# Motor_Driver.net
KiCad netlist of a schematic drawn in EAGLE
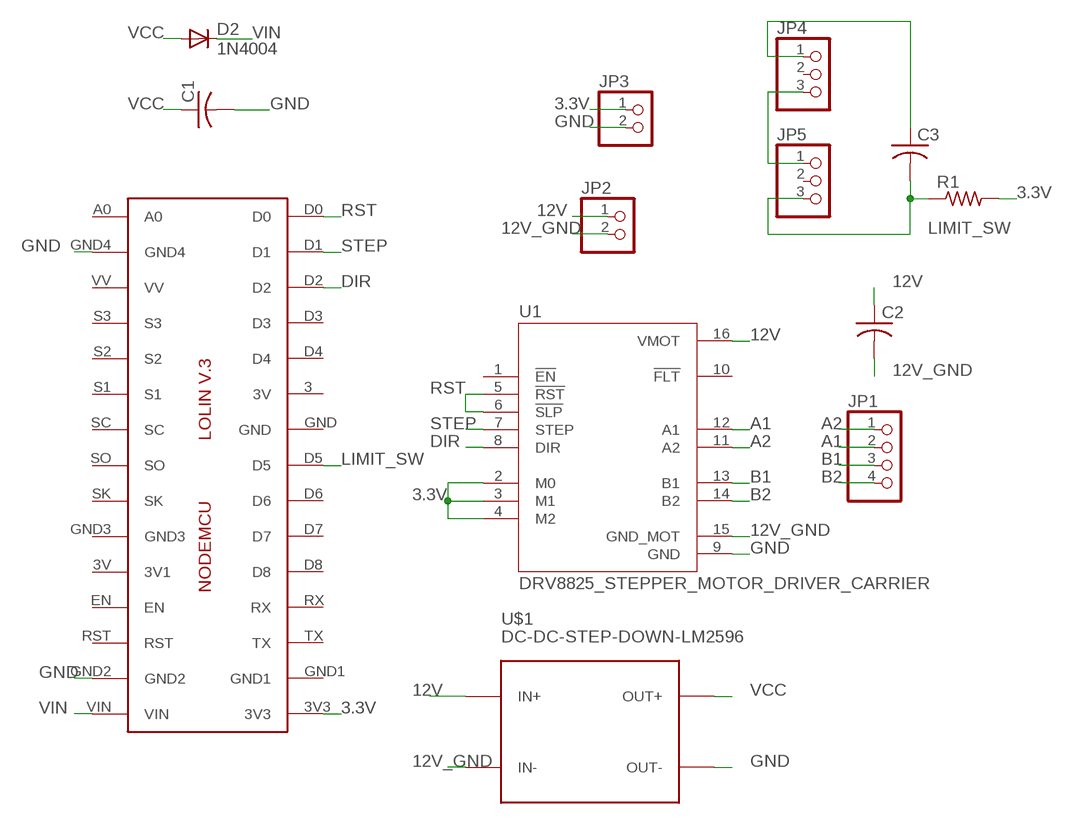
[diagram p0: schematic, sheet 1]

(export (version "E")
  (design (tool "Eeschema 10.0.6"))
  (components
    (comp (ref "C1")
      (value "C-US025-040X050")
      (footprint "eagle-import:C025-040X050")
      (libsource (lib "eagle-import") (part "C-US025-040X050"))
    )
    (comp (ref "C2")
      (value "C-US050-035X075")
      (footprint "eagle-import:C050-035X075")
      (libsource (lib "eagle-import") (part "C-US050-035X075"))
    )
    (comp (ref "C3")
      (value "C-US050-035X075")
      (footprint "eagle-import:C050-035X075")
      (libsource (lib "eagle-import") (part "C-US050-035X075"))
    )
    (comp (ref "D2")
      (value "1N4004")
      (footprint "eagle-import:DO41-10")
      (libsource (lib "eagle-import") (part "1N4004"))
    )
    (comp (ref "IC1")
      (value "LOLINV3")
      (footprint "eagle-import:LOLINV3")
      (libsource (lib "eagle-import") (part "LOLINV3"))
    )
    (comp (ref "JP1")
      (value "PINHD-1X4")
      (footprint "eagle-import:1X04")
      (libsource (lib "eagle-import") (part "PINHD-1X4"))
    )
    (comp (ref "JP2")
      (value "PINHD-1X2")
      (footprint "eagle-import:1X02")
      (libsource (lib "eagle-import") (part "PINHD-1X2"))
    )
    (comp (ref "JP3")
      (value "PINHD-1X2")
      (footprint "eagle-import:1X02")
      (libsource (lib "eagle-import") (part "PINHD-1X2"))
    )
    (comp (ref "JP4")
      (value "PINHD-1X3CB")
      (footprint "eagle-import:1X03-CLEANBIG")
      (libsource (lib "eagle-import") (part "PINHD-1X3CB"))
    )
    (comp (ref "JP5")
      (value "PINHD-1X3CB")
      (footprint "eagle-import:1X03-CLEANBIG")
      (libsource (lib "eagle-import") (part "PINHD-1X3CB"))
    )
    (comp (ref "R1")
      (value "R-US_V234/12")
      (footprint "eagle-import:V234_12")
      (libsource (lib "eagle-import") (part "R-US_V234/12"))
    )
    (comp (ref "U$1")
      (value "DC-DC-STEP-DOWN-LM2596")
      (footprint "eagle-import:DC-DC-STEP-DOWN-LM2596")
      (libsource (lib "eagle-import") (part "DC-DC-STEP-DOWN-LM2596"))
    )
    (comp (ref "U1")
      (value "DRV8825_STEPPER_MOTOR_DRIVER_CARRIER")
      (footprint "eagle-import:IC_DRV8825_STEPPER_MOTOR_DRIVER_CARRIER")
      (fields (field (name "MF") "Pololu") (field (name "MP") "DRV8825 STEPPER MOTOR DRIVER CARRIER"))
      (libsource (lib "eagle-import") (part "DRV8825_STEPPER_MOTOR_DRIVER_CARRIER"))
    )
  )
  (nets
    (net (code "1") (name "/3.3V") (class "Default")
      (node (ref "IC1") (pin "3V3") (pinfunction "3V3_3V3") (pintype "bidirectional"))
      (node (ref "JP3") (pin "1") (pinfunction "1_1") (pintype "passive"))
      (node (ref "R1") (pin "2") (pinfunction "2_2") (pintype "passive"))
      (node (ref "U1") (pin "2") (pinfunction "M0_2") (pintype "input"))
      (node (ref "U1") (pin "3") (pinfunction "M1_3") (pintype "input"))
      (node (ref "U1") (pin "4") (pinfunction "M2_4") (pintype "input"))
    )
    (net (code "2") (name "/12V") (class "Default")
      (node (ref "C2") (pin "1") (pinfunction "1_1") (pintype "passive"))
      (node (ref "JP2") (pin "1") (pinfunction "1_1") (pintype "passive"))
      (node (ref "U$1") (pin "IN+") (pinfunction "IN+_IN+") (pintype "bidirectional"))
      (node (ref "U1") (pin "16") (pinfunction "VMOT_16") (pintype "power_in"))
    )
    (net (code "3") (name "/12V_GND") (class "Default")
      (node (ref "C2") (pin "2") (pinfunction "2_2") (pintype "passive"))
      (node (ref "JP2") (pin "2") (pinfunction "2_2") (pintype "passive"))
      (node (ref "U$1") (pin "IN-") (pinfunction "IN-_IN-") (pintype "bidirectional"))
      (node (ref "U1") (pin "15") (pinfunction "GND_MOT_15") (pintype "power_in"))
    )
    (net (code "4") (name "/A1") (class "Default")
      (node (ref "JP1") (pin "2") (pinfunction "2_2") (pintype "passive"))
      (node (ref "U1") (pin "12") (pinfunction "A1_12") (pintype "output"))
    )
    (net (code "5") (name "/A2") (class "Default")
      (node (ref "JP1") (pin "1") (pinfunction "1_1") (pintype "passive"))
      (node (ref "U1") (pin "11") (pinfunction "A2_11") (pintype "output"))
    )
    (net (code "6") (name "/B1") (class "Default")
      (node (ref "JP1") (pin "3") (pinfunction "3_3") (pintype "passive"))
      (node (ref "U1") (pin "13") (pinfunction "B1_13") (pintype "output"))
    )
    (net (code "7") (name "/B2") (class "Default")
      (node (ref "JP1") (pin "4") (pinfunction "4_4") (pintype "passive"))
      (node (ref "U1") (pin "14") (pinfunction "B2_14") (pintype "output"))
    )
    (net (code "8") (name "/DIR") (class "Default")
      (node (ref "IC1") (pin "D2") (pinfunction "D2_D2") (pintype "bidirectional"))
      (node (ref "U1") (pin "8") (pinfunction "DIR_8") (pintype "input"))
    )
    (net (code "9") (name "/GND") (class "Default")
      (node (ref "C1") (pin "2") (pinfunction "2_2") (pintype "passive"))
      (node (ref "IC1") (pin "GND2") (pinfunction "GND2_GND2") (pintype "bidirectional"))
      (node (ref "IC1") (pin "GND4") (pinfunction "GND4_GND4") (pintype "bidirectional"))
      (node (ref "JP3") (pin "2") (pinfunction "2_2") (pintype "passive"))
      (node (ref "U$1") (pin "OUT-") (pinfunction "OUT-_OUT-") (pintype "bidirectional"))
      (node (ref "U1") (pin "9") (pinfunction "GND_9") (pintype "power_in"))
    )
    (net (code "10") (name "/LIMIT_SW") (class "Default")
      (node (ref "C3") (pin "2") (pinfunction "2_2") (pintype "passive"))
      (node (ref "IC1") (pin "D5") (pinfunction "D5_D5") (pintype "bidirectional"))
      (node (ref "JP5") (pin "3") (pinfunction "3_3") (pintype "passive"))
      (node (ref "R1") (pin "1") (pinfunction "1_1") (pintype "passive"))
    )
    (net (code "11") (name "/RST") (class "Default")
      (node (ref "IC1") (pin "D0") (pinfunction "D0_D0") (pintype "bidirectional"))
      (node (ref "U1") (pin "5") (pinfunction "~{RST}_5") (pintype "input"))
      (node (ref "U1") (pin "6") (pinfunction "~{SLP}_6") (pintype "input"))
    )
    (net (code "12") (name "/STEP") (class "Default")
      (node (ref "IC1") (pin "D1") (pinfunction "D1_D1") (pintype "bidirectional"))
      (node (ref "U1") (pin "7") (pinfunction "STEP_7") (pintype "input"))
    )
    (net (code "13") (name "/VCC") (class "Default")
      (node (ref "C1") (pin "1") (pinfunction "1_1") (pintype "passive"))
      (node (ref "D2") (pin "A") (pinfunction "A_A") (pintype "passive"))
      (node (ref "U$1") (pin "OUT+") (pinfunction "OUT+_OUT+") (pintype "bidirectional"))
    )
    (net (code "14") (name "/VIN") (class "Default")
      (node (ref "D2") (pin "C") (pinfunction "C_C") (pintype "passive"))
      (node (ref "IC1") (pin "VIN") (pinfunction "VIN_VIN") (pintype "bidirectional"))
    )
    (net (code "15") (name "Net-(C3-Pad1)") (class "Default")
      (node (ref "C3") (pin "1") (pinfunction "1_1") (pintype "passive"))
      (node (ref "JP4") (pin "1") (pinfunction "1_1") (pintype "passive"))
    )
    (net (code "16") (name "Net-(JP4-Pad3)") (class "Default")
      (node (ref "JP4") (pin "3") (pinfunction "3_3") (pintype "passive"))
      (node (ref "JP5") (pin "1") (pinfunction "1_1") (pintype "passive"))
    )
    (net (code "17") (name "unconnected-(IC1-3V-Pad3)") (class "Default")
      (node (ref "IC1") (pin "3") (pinfunction "3V_3") (pintype "bidirectional"))
    )
    (net (code "18") (name "unconnected-(IC1-3V1-Pad3V)") (class "Default")
      (node (ref "IC1") (pin "3V") (pinfunction "3V1_3V") (pintype "bidirectional"))
    )
    (net (code "19") (name "unconnected-(IC1-PadA0)") (class "Default")
      (node (ref "IC1") (pin "A0") (pinfunction "A0_A0") (pintype "bidirectional"))
    )
    (net (code "20") (name "unconnected-(IC1-PadD3)") (class "Default")
      (node (ref "IC1") (pin "D3") (pinfunction "D3_D3") (pintype "bidirectional"))
    )
    (net (code "21") (name "unconnected-(IC1-PadD4)") (class "Default")
      (node (ref "IC1") (pin "D4") (pinfunction "D4_D4") (pintype "bidirectional"))
    )
    (net (code "22") (name "unconnected-(IC1-PadD6)") (class "Default")
      (node (ref "IC1") (pin "D6") (pinfunction "D6_D6") (pintype "bidirectional"))
    )
    (net (code "23") (name "unconnected-(IC1-PadD7)") (class "Default")
      (node (ref "IC1") (pin "D7") (pinfunction "D7_D7") (pintype "bidirectional"))
    )
    (net (code "24") (name "unconnected-(IC1-PadD8)") (class "Default")
      (node (ref "IC1") (pin "D8") (pinfunction "D8_D8") (pintype "bidirectional"))
    )
    (net (code "25") (name "unconnected-(IC1-PadEN)") (class "Default")
      (node (ref "IC1") (pin "EN") (pinfunction "EN_EN") (pintype "bidirectional"))
    )
    (net (code "26") (name "unconnected-(IC1-PadGND)") (class "Default")
      (node (ref "IC1") (pin "GND") (pinfunction "GND_GND") (pintype "bidirectional"))
    )
    (net (code "27") (name "unconnected-(IC1-PadGND1)") (class "Default")
      (node (ref "IC1") (pin "GND1") (pinfunction "GND1_GND1") (pintype "bidirectional"))
    )
    (net (code "28") (name "unconnected-(IC1-PadGND3)") (class "Default")
      (node (ref "IC1") (pin "GND3") (pinfunction "GND3_GND3") (pintype "bidirectional"))
    )
    (net (code "29") (name "unconnected-(IC1-PadRST)") (class "Default")
      (node (ref "IC1") (pin "RST") (pinfunction "RST_RST") (pintype "bidirectional"))
    )
    (net (code "30") (name "unconnected-(IC1-PadRX)") (class "Default")
      (node (ref "IC1") (pin "RX") (pinfunction "RX_RX") (pintype "bidirectional"))
    )
    (net (code "31") (name "unconnected-(IC1-PadS1)") (class "Default")
      (node (ref "IC1") (pin "S1") (pinfunction "S1_S1") (pintype "bidirectional"))
    )
    (net (code "32") (name "unconnected-(IC1-PadS2)") (class "Default")
      (node (ref "IC1") (pin "S2") (pinfunction "S2_S2") (pintype "bidirectional"))
    )
    (net (code "33") (name "unconnected-(IC1-PadS3)") (class "Default")
      (node (ref "IC1") (pin "S3") (pinfunction "S3_S3") (pintype "bidirectional"))
    )
    (net (code "34") (name "unconnected-(IC1-PadSC)") (class "Default")
      (node (ref "IC1") (pin "SC") (pinfunction "SC_SC") (pintype "bidirectional"))
    )
    (net (code "35") (name "unconnected-(IC1-PadSK)") (class "Default")
      (node (ref "IC1") (pin "SK") (pinfunction "SK_SK") (pintype "bidirectional"))
    )
    (net (code "36") (name "unconnected-(IC1-PadSO)") (class "Default")
      (node (ref "IC1") (pin "SO") (pinfunction "SO_SO") (pintype "bidirectional"))
    )
    (net (code "37") (name "unconnected-(IC1-PadTX)") (class "Default")
      (node (ref "IC1") (pin "TX") (pinfunction "TX_TX") (pintype "bidirectional"))
    )
    (net (code "38") (name "unconnected-(IC1-PadVV)") (class "Default")
      (node (ref "IC1") (pin "VV") (pinfunction "VV_VV") (pintype "bidirectional"))
    )
    (net (code "39") (name "unconnected-(JP4-Pad2)") (class "Default")
      (node (ref "JP4") (pin "2") (pinfunction "2_2") (pintype "passive"))
    )
    (net (code "40") (name "unconnected-(JP5-Pad2)") (class "Default")
      (node (ref "JP5") (pin "2") (pinfunction "2_2") (pintype "passive"))
    )
    (net (code "41") (name "unconnected-(U1-~{EN}-Pad1)") (class "Default")
      (node (ref "U1") (pin "1") (pinfunction "~{EN}_1") (pintype "input"))
    )
    (net (code "42") (name "unconnected-(U1-~{FLT}-Pad10)") (class "Default")
      (node (ref "U1") (pin "10") (pinfunction "~{FLT}_10") (pintype "output"))
    )
  )
)
